# mach_giua_ben_trai.net
KiCad netlist of a schematic drawn in Altium Designer
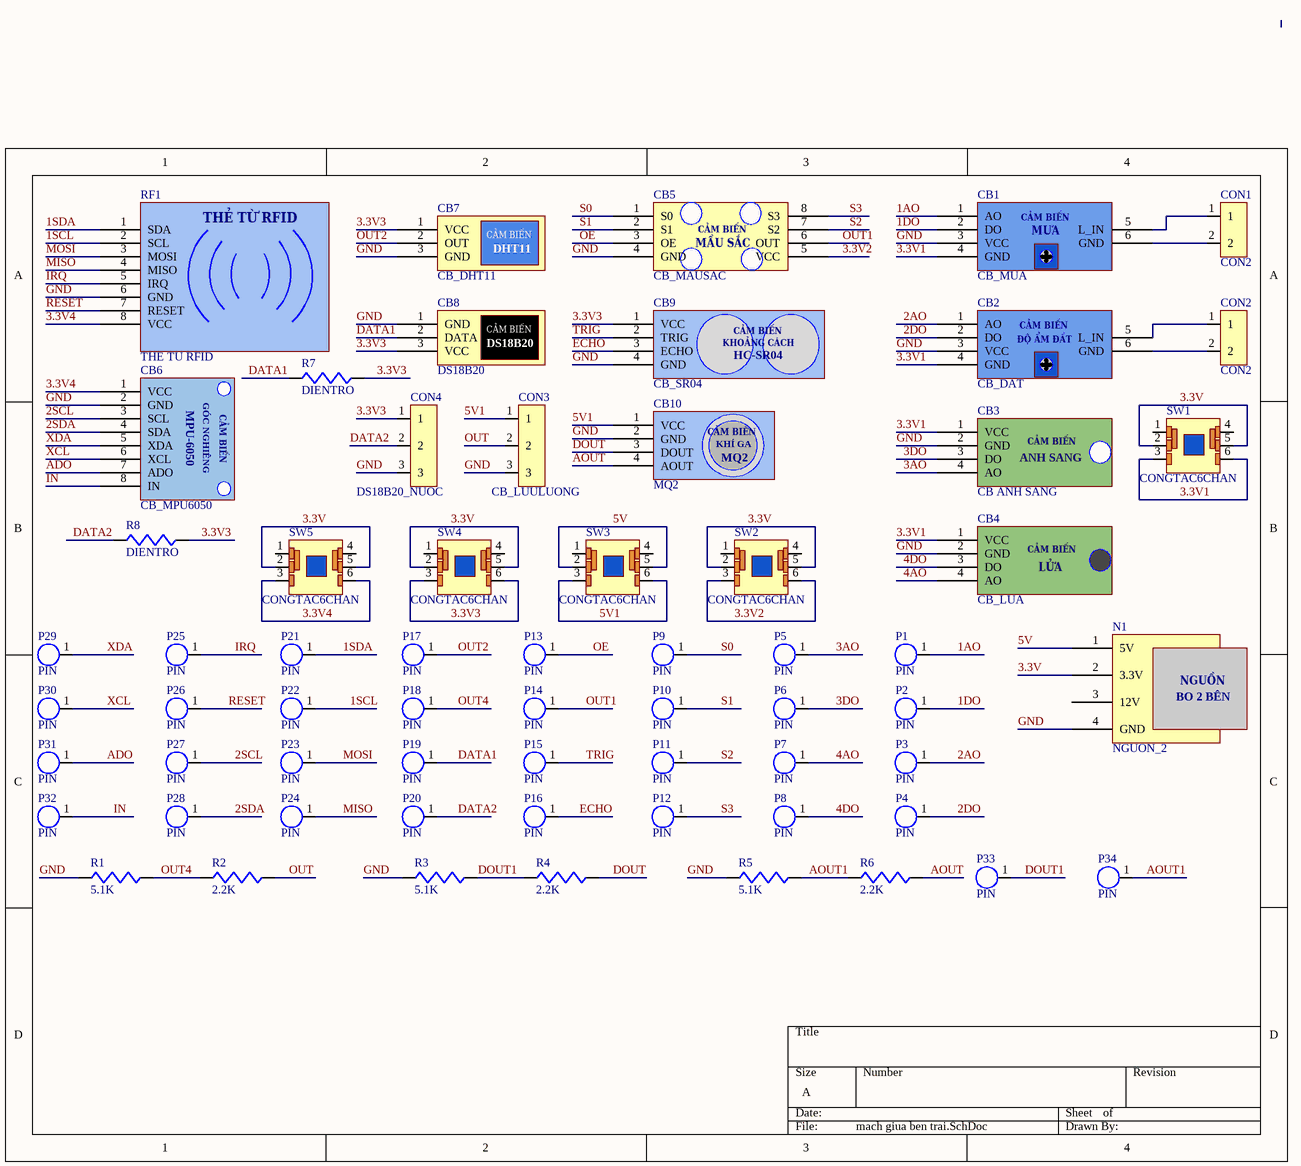
[diagram p0: mach giua ben trai.SchDoc]

(export (version "E")
  (design (tool "Eeschema 10.0.6"))
  (components
    (comp (ref "CB1") (value "CB_MUA") (footprint "CB_MUA") (libsource (lib "CB_MUA_NL") (part "CB_MUA")))
    (comp (ref "CB2") (value "CB_DAT") (footprint "CB_MUA") (libsource (lib "CB_DOAMDAT_NL") (part "CB_DAT")))
    (comp (ref "CB3")
      (value "CB ANH SANG")
      (footprint "CB ANH SANG")
      (libsource (lib "CB_ANH_SANG_NL") (part "CB ANH SANG"))
    )
    (comp (ref "CB4") (value "CB_LUA") (footprint "CB_LUA") (libsource (lib "CB_LUA_NL") (part "CB_LUA")))
    (comp (ref "CB5")
      (value "CB_MAUSAC")
      (footprint "CB_MAUSAC")
      (libsource (lib "CB_MAUSAC") (part "CB_MAUSAC"))
    )
    (comp (ref "CB6")
      (value "CB_MPU6050")
      (footprint "CB_MPU6050")
      (libsource (lib "CB_GOCNGHIENG_NL") (part "CB_MPU6050"))
    )
    (comp (ref "CB7")
      (value "CB_DHT11")
      (footprint "CB_DHT11")
      (libsource (lib "CB_DHT11_NL") (part "CB_DHT11"))
    )
    (comp (ref "CB8")
      (value "DS18B20")
      (footprint "DS18B20")
      (libsource (lib "CB_DS18B20_NL") (part "DS18B20"))
    )
    (comp (ref "CB9")
      (value "CB_SR04")
      (footprint "CB_SR04")
      (libsource (lib "CB_KHOANGCACH_NL") (part "CB_SR04"))
    )
    (comp (ref "CB10") (value "MQ2") (footprint "MQ2") (libsource (lib "CB_MQ2_NL") (part "MQ2")))
    (comp (ref "CON1") (value "CON2") (footprint "CON2") (libsource (lib "CON2_NL") (part "CON2")))
    (comp (ref "CON2") (value "CON2") (footprint "CON2") (libsource (lib "CON2_NL") (part "CON2")))
    (comp (ref "CON3") (value "CB_LUULUONG") (footprint "CON3") (libsource (lib "CON3_NL") (part "CON3")))
    (comp (ref "CON4") (value "DS18B20_NUOC") (footprint "CON3") (libsource (lib "CON3_NL") (part "CON3")))
    (comp (ref "N1")
      (value "NGUON_2")
      (footprint "NGUON_2")
      (libsource (lib "NGUON_BO2BEN_NL") (part "NGUON_2"))
    )
    (comp (ref "P1") (value "PIN") (footprint "PIN1") (libsource (lib "PIN1_NL") (part "PIN")))
    (comp (ref "P2") (value "PIN") (footprint "PIN1") (libsource (lib "PIN1_NL") (part "PIN")))
    (comp (ref "P3") (value "PIN") (footprint "PIN1") (libsource (lib "PIN1_NL") (part "PIN")))
    (comp (ref "P4") (value "PIN") (footprint "PIN1") (libsource (lib "PIN1_NL") (part "PIN")))
    (comp (ref "P5") (value "PIN") (footprint "PIN1") (libsource (lib "PIN1_NL") (part "PIN")))
    (comp (ref "P6") (value "PIN") (footprint "PIN1") (libsource (lib "PIN1_NL") (part "PIN")))
    (comp (ref "P7") (value "PIN") (footprint "PIN1") (libsource (lib "PIN1_NL") (part "PIN")))
    (comp (ref "P8") (value "PIN") (footprint "PIN1") (libsource (lib "PIN1_NL") (part "PIN")))
    (comp (ref "P9") (value "PIN") (footprint "PIN1") (libsource (lib "PIN1_NL") (part "PIN")))
    (comp (ref "P10") (value "PIN") (footprint "PIN1") (libsource (lib "PIN1_NL") (part "PIN")))
    (comp (ref "P11") (value "PIN") (footprint "PIN1") (libsource (lib "PIN1_NL") (part "PIN")))
    (comp (ref "P12") (value "PIN") (footprint "PIN1") (libsource (lib "PIN1_NL") (part "PIN")))
    (comp (ref "P13") (value "PIN") (footprint "PIN1") (libsource (lib "PIN1_NL") (part "PIN")))
    (comp (ref "P14") (value "PIN") (footprint "PIN1") (libsource (lib "PIN1_NL") (part "PIN")))
    (comp (ref "P15") (value "PIN") (footprint "PIN1") (libsource (lib "PIN1_NL") (part "PIN")))
    (comp (ref "P16") (value "PIN") (footprint "PIN1") (libsource (lib "PIN1_NL") (part "PIN")))
    (comp (ref "P17") (value "PIN") (footprint "PIN1") (libsource (lib "PIN1_NL") (part "PIN")))
    (comp (ref "P18") (value "PIN") (footprint "PIN1") (libsource (lib "PIN1_NL") (part "PIN")))
    (comp (ref "P19") (value "PIN") (footprint "PIN1") (libsource (lib "PIN1_NL") (part "PIN")))
    (comp (ref "P20") (value "PIN") (footprint "PIN1") (libsource (lib "PIN1_NL") (part "PIN")))
    (comp (ref "P21") (value "PIN") (footprint "PIN1") (libsource (lib "PIN1_NL") (part "PIN")))
    (comp (ref "P22") (value "PIN") (footprint "PIN1") (libsource (lib "PIN1_NL") (part "PIN")))
    (comp (ref "P23") (value "PIN") (footprint "PIN1") (libsource (lib "PIN1_NL") (part "PIN")))
    (comp (ref "P24") (value "PIN") (footprint "PIN1") (libsource (lib "PIN1_NL") (part "PIN")))
    (comp (ref "P25") (value "PIN") (footprint "PIN1") (libsource (lib "PIN1_NL") (part "PIN")))
    (comp (ref "P26") (value "PIN") (footprint "PIN1") (libsource (lib "PIN1_NL") (part "PIN")))
    (comp (ref "P27") (value "PIN") (footprint "PIN1") (libsource (lib "PIN1_NL") (part "PIN")))
    (comp (ref "P28") (value "PIN") (footprint "PIN1") (libsource (lib "PIN1_NL") (part "PIN")))
    (comp (ref "P29") (value "PIN") (footprint "PIN1") (libsource (lib "PIN1_NL") (part "PIN")))
    (comp (ref "P30") (value "PIN") (footprint "PIN1") (libsource (lib "PIN1_NL") (part "PIN")))
    (comp (ref "P31") (value "PIN") (footprint "PIN1") (libsource (lib "PIN1_NL") (part "PIN")))
    (comp (ref "P32") (value "PIN") (footprint "PIN1") (libsource (lib "PIN1_NL") (part "PIN")))
    (comp (ref "P33") (value "PIN") (footprint "PIN1") (libsource (lib "PIN1_NL") (part "PIN")))
    (comp (ref "P34") (value "PIN") (footprint "PIN1") (libsource (lib "PIN1_NL") (part "PIN")))
    (comp (ref "R1") (value "5.1K") (footprint "DIENTRO") (libsource (lib "DIEN_TRO_NL") (part "DIENTRO")))
    (comp (ref "R2") (value "2.2K") (footprint "DIENTRO") (libsource (lib "DIEN_TRO_NL") (part "DIENTRO")))
    (comp (ref "R3") (value "5.1K") (footprint "DIENTRO") (libsource (lib "DIEN_TRO_NL") (part "DIENTRO")))
    (comp (ref "R4") (value "2.2K") (footprint "DIENTRO") (libsource (lib "DIEN_TRO_NL") (part "DIENTRO")))
    (comp (ref "R5") (value "5.1K") (footprint "DIENTRO") (libsource (lib "DIEN_TRO_NL") (part "DIENTRO")))
    (comp (ref "R6") (value "2.2K") (footprint "DIENTRO") (libsource (lib "DIEN_TRO_NL") (part "DIENTRO")))
    (comp (ref "R7") (value "DIENTRO") (footprint "DIENTRO") (libsource (lib "DIEN_TRO_NL") (part "DIENTRO")))
    (comp (ref "R8") (value "DIENTRO") (footprint "DIENTRO") (libsource (lib "DIEN_TRO_NL") (part "DIENTRO")))
    (comp (ref "RF1")
      (value "THE TU RFID")
      (footprint "THE TU RFID")
      (libsource (lib "THE_TU_RFID_NL") (part "THE TU RFID"))
    )
    (comp (ref "SW1")
      (value "CONGTAC6CHAN")
      (footprint "CONGTAC6CHAN")
      (libsource (lib "CONGTAC6CHAN_NL") (part "CONGTAC6CHAN"))
    )
    (comp (ref "SW2")
      (value "CONGTAC6CHAN")
      (footprint "CONGTAC6CHAN")
      (libsource (lib "CONGTAC6CHAN_NL") (part "CONGTAC6CHAN"))
    )
    (comp (ref "SW3")
      (value "CONGTAC6CHAN")
      (footprint "CONGTAC6CHAN")
      (libsource (lib "CONGTAC6CHAN_NL") (part "CONGTAC6CHAN"))
    )
    (comp (ref "SW4")
      (value "CONGTAC6CHAN")
      (footprint "CONGTAC6CHAN")
      (libsource (lib "CONGTAC6CHAN_NL") (part "CONGTAC6CHAN"))
    )
    (comp (ref "SW5")
      (value "CONGTAC6CHAN")
      (footprint "CONGTAC6CHAN")
      (libsource (lib "CONGTAC6CHAN_NL") (part "CONGTAC6CHAN"))
    )
  )
  (nets
    (net (code "1") (name "/1AO") (class "Default")
      (node (ref "CB1") (pin "1") (pinfunction "AO_1") (pintype "passive"))
      (node (ref "P1") (pin "1") (pinfunction "1_1") (pintype "passive"))
    )
    (net (code "2") (name "/1DO") (class "Default")
      (node (ref "CB1") (pin "2") (pinfunction "DO_2") (pintype "passive"))
      (node (ref "P2") (pin "1") (pinfunction "1_1") (pintype "passive"))
    )
    (net (code "3") (name "/1SCL") (class "Default")
      (node (ref "P22") (pin "1") (pinfunction "1_1") (pintype "passive"))
      (node (ref "RF1") (pin "2") (pinfunction "SCL_2") (pintype "passive"))
    )
    (net (code "4") (name "/1SDA") (class "Default")
      (node (ref "P21") (pin "1") (pinfunction "1_1") (pintype "passive"))
      (node (ref "RF1") (pin "1") (pinfunction "SDA_1") (pintype "passive"))
    )
    (net (code "5") (name "/2AO") (class "Default")
      (node (ref "CB2") (pin "1") (pinfunction "AO_1") (pintype "passive"))
      (node (ref "P3") (pin "1") (pinfunction "1_1") (pintype "passive"))
    )
    (net (code "6") (name "/2DO") (class "Default")
      (node (ref "CB2") (pin "2") (pinfunction "DO_2") (pintype "passive"))
      (node (ref "P4") (pin "1") (pinfunction "1_1") (pintype "passive"))
    )
    (net (code "7") (name "/2SCL") (class "Default")
      (node (ref "CB6") (pin "3") (pinfunction "SCL_3") (pintype "passive"))
      (node (ref "P27") (pin "1") (pinfunction "1_1") (pintype "passive"))
    )
    (net (code "8") (name "/2SDA") (class "Default")
      (node (ref "CB6") (pin "4") (pinfunction "SDA_4") (pintype "passive"))
      (node (ref "P28") (pin "1") (pinfunction "1_1") (pintype "passive"))
    )
    (net (code "9") (name "/3.3V") (class "Default")
      (node (ref "N1") (pin "2") (pinfunction "3.3V_2") (pintype "passive"))
      (node (ref "SW1") (pin "2") (pintype "passive"))
      (node (ref "SW1") (pin "5") (pintype "passive"))
      (node (ref "SW2") (pin "2") (pintype "passive"))
      (node (ref "SW2") (pin "5") (pintype "passive"))
      (node (ref "SW4") (pin "2") (pintype "passive"))
      (node (ref "SW4") (pin "5") (pintype "passive"))
      (node (ref "SW5") (pin "2") (pintype "passive"))
      (node (ref "SW5") (pin "5") (pintype "passive"))
    )
    (net (code "10") (name "/3.3V1") (class "Default")
      (node (ref "CB1") (pin "4") (pinfunction "GND_4") (pintype "passive"))
      (node (ref "CB2") (pin "4") (pinfunction "GND_4") (pintype "passive"))
      (node (ref "CB3") (pin "1") (pinfunction "VCC_1") (pintype "passive"))
      (node (ref "CB4") (pin "1") (pinfunction "VCC_1") (pintype "passive"))
      (node (ref "SW1") (pin "3") (pintype "passive"))
      (node (ref "SW1") (pin "6") (pintype "passive"))
    )
    (net (code "11") (name "/3.3V2") (class "Default")
      (node (ref "CB5") (pin "5") (pinfunction "VCC_5") (pintype "passive"))
      (node (ref "SW2") (pin "3") (pintype "passive"))
      (node (ref "SW2") (pin "6") (pintype "passive"))
    )
    (net (code "12") (name "/3.3V3") (class "Default")
      (node (ref "CB7") (pin "1") (pinfunction "VCC_1") (pintype "passive"))
      (node (ref "CB8") (pin "3") (pinfunction "VCC_3") (pintype "passive"))
      (node (ref "CB9") (pin "1") (pinfunction "VCC_1") (pintype "passive"))
      (node (ref "CON4") (pin "1") (pinfunction "1_1") (pintype "passive"))
      (node (ref "R7") (pin "2") (pinfunction "2_2") (pintype "passive"))
      (node (ref "R8") (pin "2") (pinfunction "2_2") (pintype "passive"))
      (node (ref "SW4") (pin "3") (pintype "passive"))
      (node (ref "SW4") (pin "6") (pintype "passive"))
    )
    (net (code "13") (name "/3.3V4") (class "Default")
      (node (ref "CB6") (pin "1") (pinfunction "VCC_1") (pintype "passive"))
      (node (ref "RF1") (pin "8") (pinfunction "VCC_8") (pintype "passive"))
      (node (ref "SW5") (pin "3") (pintype "passive"))
      (node (ref "SW5") (pin "6") (pintype "passive"))
    )
    (net (code "14") (name "/3AO") (class "Default")
      (node (ref "CB3") (pin "4") (pinfunction "AO_4") (pintype "passive"))
      (node (ref "P5") (pin "1") (pinfunction "1_1") (pintype "passive"))
    )
    (net (code "15") (name "/3DO") (class "Default")
      (node (ref "CB3") (pin "3") (pinfunction "DO_3") (pintype "passive"))
      (node (ref "P6") (pin "1") (pinfunction "1_1") (pintype "passive"))
    )
    (net (code "16") (name "/4AO") (class "Default")
      (node (ref "CB4") (pin "4") (pinfunction "AO_4") (pintype "passive"))
      (node (ref "P7") (pin "1") (pinfunction "1_1") (pintype "passive"))
    )
    (net (code "17") (name "/4DO") (class "Default")
      (node (ref "CB4") (pin "3") (pinfunction "DO_3") (pintype "passive"))
      (node (ref "P8") (pin "1") (pinfunction "1_1") (pintype "passive"))
    )
    (net (code "18") (name "/5V") (class "Default")
      (node (ref "N1") (pin "1") (pinfunction "5V_1") (pintype "passive"))
      (node (ref "SW3") (pin "2") (pintype "passive"))
      (node (ref "SW3") (pin "5") (pintype "passive"))
    )
    (net (code "19") (name "/5V1") (class "Default")
      (node (ref "CB10") (pin "1") (pinfunction "VCC_1") (pintype "passive"))
      (node (ref "CON3") (pin "1") (pinfunction "1_1") (pintype "passive"))
      (node (ref "SW3") (pin "3") (pintype "passive"))
      (node (ref "SW3") (pin "6") (pintype "passive"))
    )
    (net (code "20") (name "/ADO") (class "Default")
      (node (ref "CB6") (pin "7") (pinfunction "ADO_7") (pintype "passive"))
      (node (ref "P31") (pin "1") (pinfunction "1_1") (pintype "passive"))
    )
    (net (code "21") (name "/AOUT") (class "Default")
      (node (ref "CB10") (pin "4") (pinfunction "AOUT_4") (pintype "passive"))
      (node (ref "R6") (pin "2") (pinfunction "2_2") (pintype "passive"))
    )
    (net (code "22") (name "/AOUT1") (class "Default")
      (node (ref "P34") (pin "1") (pinfunction "1_1") (pintype "passive"))
      (node (ref "R5") (pin "2") (pinfunction "2_2") (pintype "passive"))
      (node (ref "R6") (pin "1") (pinfunction "1_1") (pintype "passive"))
    )
    (net (code "23") (name "/DATA1") (class "Default")
      (node (ref "CB8") (pin "2") (pinfunction "DATA_2") (pintype "passive"))
      (node (ref "P19") (pin "1") (pinfunction "1_1") (pintype "passive"))
      (node (ref "R7") (pin "1") (pinfunction "1_1") (pintype "passive"))
    )
    (net (code "24") (name "/DATA2") (class "Default")
      (node (ref "CON4") (pin "2") (pinfunction "2_2") (pintype "passive"))
      (node (ref "P20") (pin "1") (pinfunction "1_1") (pintype "passive"))
      (node (ref "R8") (pin "1") (pinfunction "1_1") (pintype "passive"))
    )
    (net (code "25") (name "/DOUT") (class "Default")
      (node (ref "CB10") (pin "3") (pinfunction "DOUT_3") (pintype "passive"))
      (node (ref "R4") (pin "2") (pinfunction "2_2") (pintype "passive"))
    )
    (net (code "26") (name "/DOUT1") (class "Default")
      (node (ref "P33") (pin "1") (pinfunction "1_1") (pintype "passive"))
      (node (ref "R3") (pin "2") (pinfunction "2_2") (pintype "passive"))
      (node (ref "R4") (pin "1") (pinfunction "1_1") (pintype "passive"))
    )
    (net (code "27") (name "/ECHO") (class "Default")
      (node (ref "CB9") (pin "3") (pinfunction "ECHO_3") (pintype "passive"))
      (node (ref "P16") (pin "1") (pinfunction "1_1") (pintype "passive"))
    )
    (net (code "28") (name "/GND") (class "Default")
      (node (ref "CB1") (pin "3") (pinfunction "VCC_3") (pintype "passive"))
      (node (ref "CB10") (pin "2") (pinfunction "GND_2") (pintype "passive"))
      (node (ref "CB2") (pin "3") (pinfunction "VCC_3") (pintype "passive"))
      (node (ref "CB3") (pin "2") (pinfunction "GND_2") (pintype "passive"))
      (node (ref "CB4") (pin "2") (pinfunction "GND_2") (pintype "passive"))
      (node (ref "CB5") (pin "4") (pinfunction "GND_4") (pintype "passive"))
      (node (ref "CB6") (pin "2") (pinfunction "GND_2") (pintype "passive"))
      (node (ref "CB7") (pin "3") (pinfunction "GND_3") (pintype "passive"))
      (node (ref "CB8") (pin "1") (pinfunction "GND_1") (pintype "passive"))
      (node (ref "CB9") (pin "4") (pinfunction "GND_4") (pintype "passive"))
      (node (ref "CON3") (pin "3") (pinfunction "3_3") (pintype "passive"))
      (node (ref "CON4") (pin "3") (pinfunction "3_3") (pintype "passive"))
      (node (ref "N1") (pin "4") (pinfunction "GND_4") (pintype "passive"))
      (node (ref "R1") (pin "1") (pinfunction "1_1") (pintype "passive"))
      (node (ref "R3") (pin "1") (pinfunction "1_1") (pintype "passive"))
      (node (ref "R5") (pin "1") (pinfunction "1_1") (pintype "passive"))
      (node (ref "RF1") (pin "6") (pinfunction "GND_6") (pintype "passive"))
    )
    (net (code "29") (name "/IN") (class "Default")
      (node (ref "CB6") (pin "8") (pinfunction "IN_8") (pintype "passive"))
      (node (ref "P32") (pin "1") (pinfunction "1_1") (pintype "passive"))
    )
    (net (code "30") (name "/IRQ") (class "Default")
      (node (ref "P25") (pin "1") (pinfunction "1_1") (pintype "passive"))
      (node (ref "RF1") (pin "5") (pinfunction "IRQ_5") (pintype "passive"))
    )
    (net (code "31") (name "/MISO") (class "Default")
      (node (ref "P24") (pin "1") (pinfunction "1_1") (pintype "passive"))
      (node (ref "RF1") (pin "4") (pinfunction "MISO_4") (pintype "passive"))
    )
    (net (code "32") (name "/MOSI") (class "Default")
      (node (ref "P23") (pin "1") (pinfunction "1_1") (pintype "passive"))
      (node (ref "RF1") (pin "3") (pinfunction "MOSI_3") (pintype "passive"))
    )
    (net (code "33") (name "/OE") (class "Default")
      (node (ref "CB5") (pin "3") (pinfunction "OE_3") (pintype "passive"))
      (node (ref "P13") (pin "1") (pinfunction "1_1") (pintype "passive"))
    )
    (net (code "34") (name "/OUT") (class "Default")
      (node (ref "CON3") (pin "2") (pinfunction "2_2") (pintype "passive"))
      (node (ref "R2") (pin "2") (pinfunction "2_2") (pintype "passive"))
    )
    (net (code "35") (name "/OUT1") (class "Default")
      (node (ref "CB5") (pin "6") (pinfunction "OUT_6") (pintype "passive"))
      (node (ref "P14") (pin "1") (pinfunction "1_1") (pintype "passive"))
    )
    (net (code "36") (name "/OUT2") (class "Default")
      (node (ref "CB7") (pin "2") (pinfunction "OUT_2") (pintype "passive"))
      (node (ref "P17") (pin "1") (pinfunction "1_1") (pintype "passive"))
    )
    (net (code "37") (name "/OUT4") (class "Default")
      (node (ref "P18") (pin "1") (pinfunction "1_1") (pintype "passive"))
      (node (ref "R1") (pin "2") (pinfunction "2_2") (pintype "passive"))
      (node (ref "R2") (pin "1") (pinfunction "1_1") (pintype "passive"))
    )
    (net (code "38") (name "/RESET") (class "Default")
      (node (ref "P26") (pin "1") (pinfunction "1_1") (pintype "passive"))
      (node (ref "RF1") (pin "7") (pinfunction "RESET_7") (pintype "passive"))
    )
    (net (code "39") (name "/S0") (class "Default")
      (node (ref "CB5") (pin "1") (pinfunction "S0_1") (pintype "passive"))
      (node (ref "P9") (pin "1") (pinfunction "1_1") (pintype "passive"))
    )
    (net (code "40") (name "/S1") (class "Default")
      (node (ref "CB5") (pin "2") (pinfunction "S1_2") (pintype "passive"))
      (node (ref "P10") (pin "1") (pinfunction "1_1") (pintype "passive"))
    )
    (net (code "41") (name "/S2") (class "Default")
      (node (ref "CB5") (pin "7") (pinfunction "S2_7") (pintype "passive"))
      (node (ref "P11") (pin "1") (pinfunction "1_1") (pintype "passive"))
    )
    (net (code "42") (name "/S3") (class "Default")
      (node (ref "CB5") (pin "8") (pinfunction "S3_8") (pintype "passive"))
      (node (ref "P12") (pin "1") (pinfunction "1_1") (pintype "passive"))
    )
    (net (code "43") (name "/TRIG") (class "Default")
      (node (ref "CB9") (pin "2") (pinfunction "TRIG_2") (pintype "passive"))
      (node (ref "P15") (pin "1") (pinfunction "1_1") (pintype "passive"))
    )
    (net (code "44") (name "/XCL") (class "Default")
      (node (ref "CB6") (pin "6") (pinfunction "XCL_6") (pintype "passive"))
      (node (ref "P30") (pin "1") (pinfunction "1_1") (pintype "passive"))
    )
    (net (code "45") (name "/XDA") (class "Default")
      (node (ref "CB6") (pin "5") (pinfunction "XDA_5") (pintype "passive"))
      (node (ref "P29") (pin "1") (pinfunction "1_1") (pintype "passive"))
    )
    (net (code "46") (name "Net-(CB1-GND-Pad6)") (class "Default")
      (node (ref "CB1") (pin "6") (pinfunction "GND_6") (pintype "passive"))
      (node (ref "CON1") (pin "2") (pinfunction "2_2") (pintype "passive"))
    )
    (net (code "47") (name "Net-(CB1-L_IN)") (class "Default")
      (node (ref "CB1") (pin "5") (pinfunction "L_IN_5") (pintype "passive"))
      (node (ref "CON1") (pin "1") (pinfunction "1_1") (pintype "passive"))
    )
    (net (code "48") (name "Net-(CB2-GND-Pad6)") (class "Default")
      (node (ref "CB2") (pin "6") (pinfunction "GND_6") (pintype "passive"))
      (node (ref "CON2") (pin "2") (pinfunction "2_2") (pintype "passive"))
    )
    (net (code "49") (name "Net-(CB2-L_IN)") (class "Default")
      (node (ref "CB2") (pin "5") (pinfunction "L_IN_5") (pintype "passive"))
      (node (ref "CON2") (pin "1") (pinfunction "1_1") (pintype "passive"))
    )
    (net (code "50") (name "unconnected-(N1-12V-Pad3)") (class "Default")
      (node (ref "N1") (pin "3") (pinfunction "12V_3") (pintype "passive"))
    )
    (net (code "51") (name "unconnected-(SW1-Pad1)") (class "Default")
      (node (ref "SW1") (pin "1") (pintype "passive"))
    )
    (net (code "52") (name "unconnected-(SW1-Pad4)") (class "Default")
      (node (ref "SW1") (pin "4") (pintype "passive"))
    )
    (net (code "53") (name "unconnected-(SW2-Pad1)") (class "Default")
      (node (ref "SW2") (pin "1") (pintype "passive"))
    )
    (net (code "54") (name "unconnected-(SW2-Pad4)") (class "Default")
      (node (ref "SW2") (pin "4") (pintype "passive"))
    )
    (net (code "55") (name "unconnected-(SW3-Pad1)") (class "Default")
      (node (ref "SW3") (pin "1") (pintype "passive"))
    )
    (net (code "56") (name "unconnected-(SW3-Pad4)") (class "Default")
      (node (ref "SW3") (pin "4") (pintype "passive"))
    )
    (net (code "57") (name "unconnected-(SW4-Pad1)") (class "Default")
      (node (ref "SW4") (pin "1") (pintype "passive"))
    )
    (net (code "58") (name "unconnected-(SW4-Pad4)") (class "Default")
      (node (ref "SW4") (pin "4") (pintype "passive"))
    )
    (net (code "59") (name "unconnected-(SW5-Pad1)") (class "Default")
      (node (ref "SW5") (pin "1") (pintype "passive"))
    )
    (net (code "60") (name "unconnected-(SW5-Pad4)") (class "Default")
      (node (ref "SW5") (pin "4") (pintype "passive"))
    )
  )
)
